# rpi_can.net
KiCad netlist of a schematic drawn in EAGLE
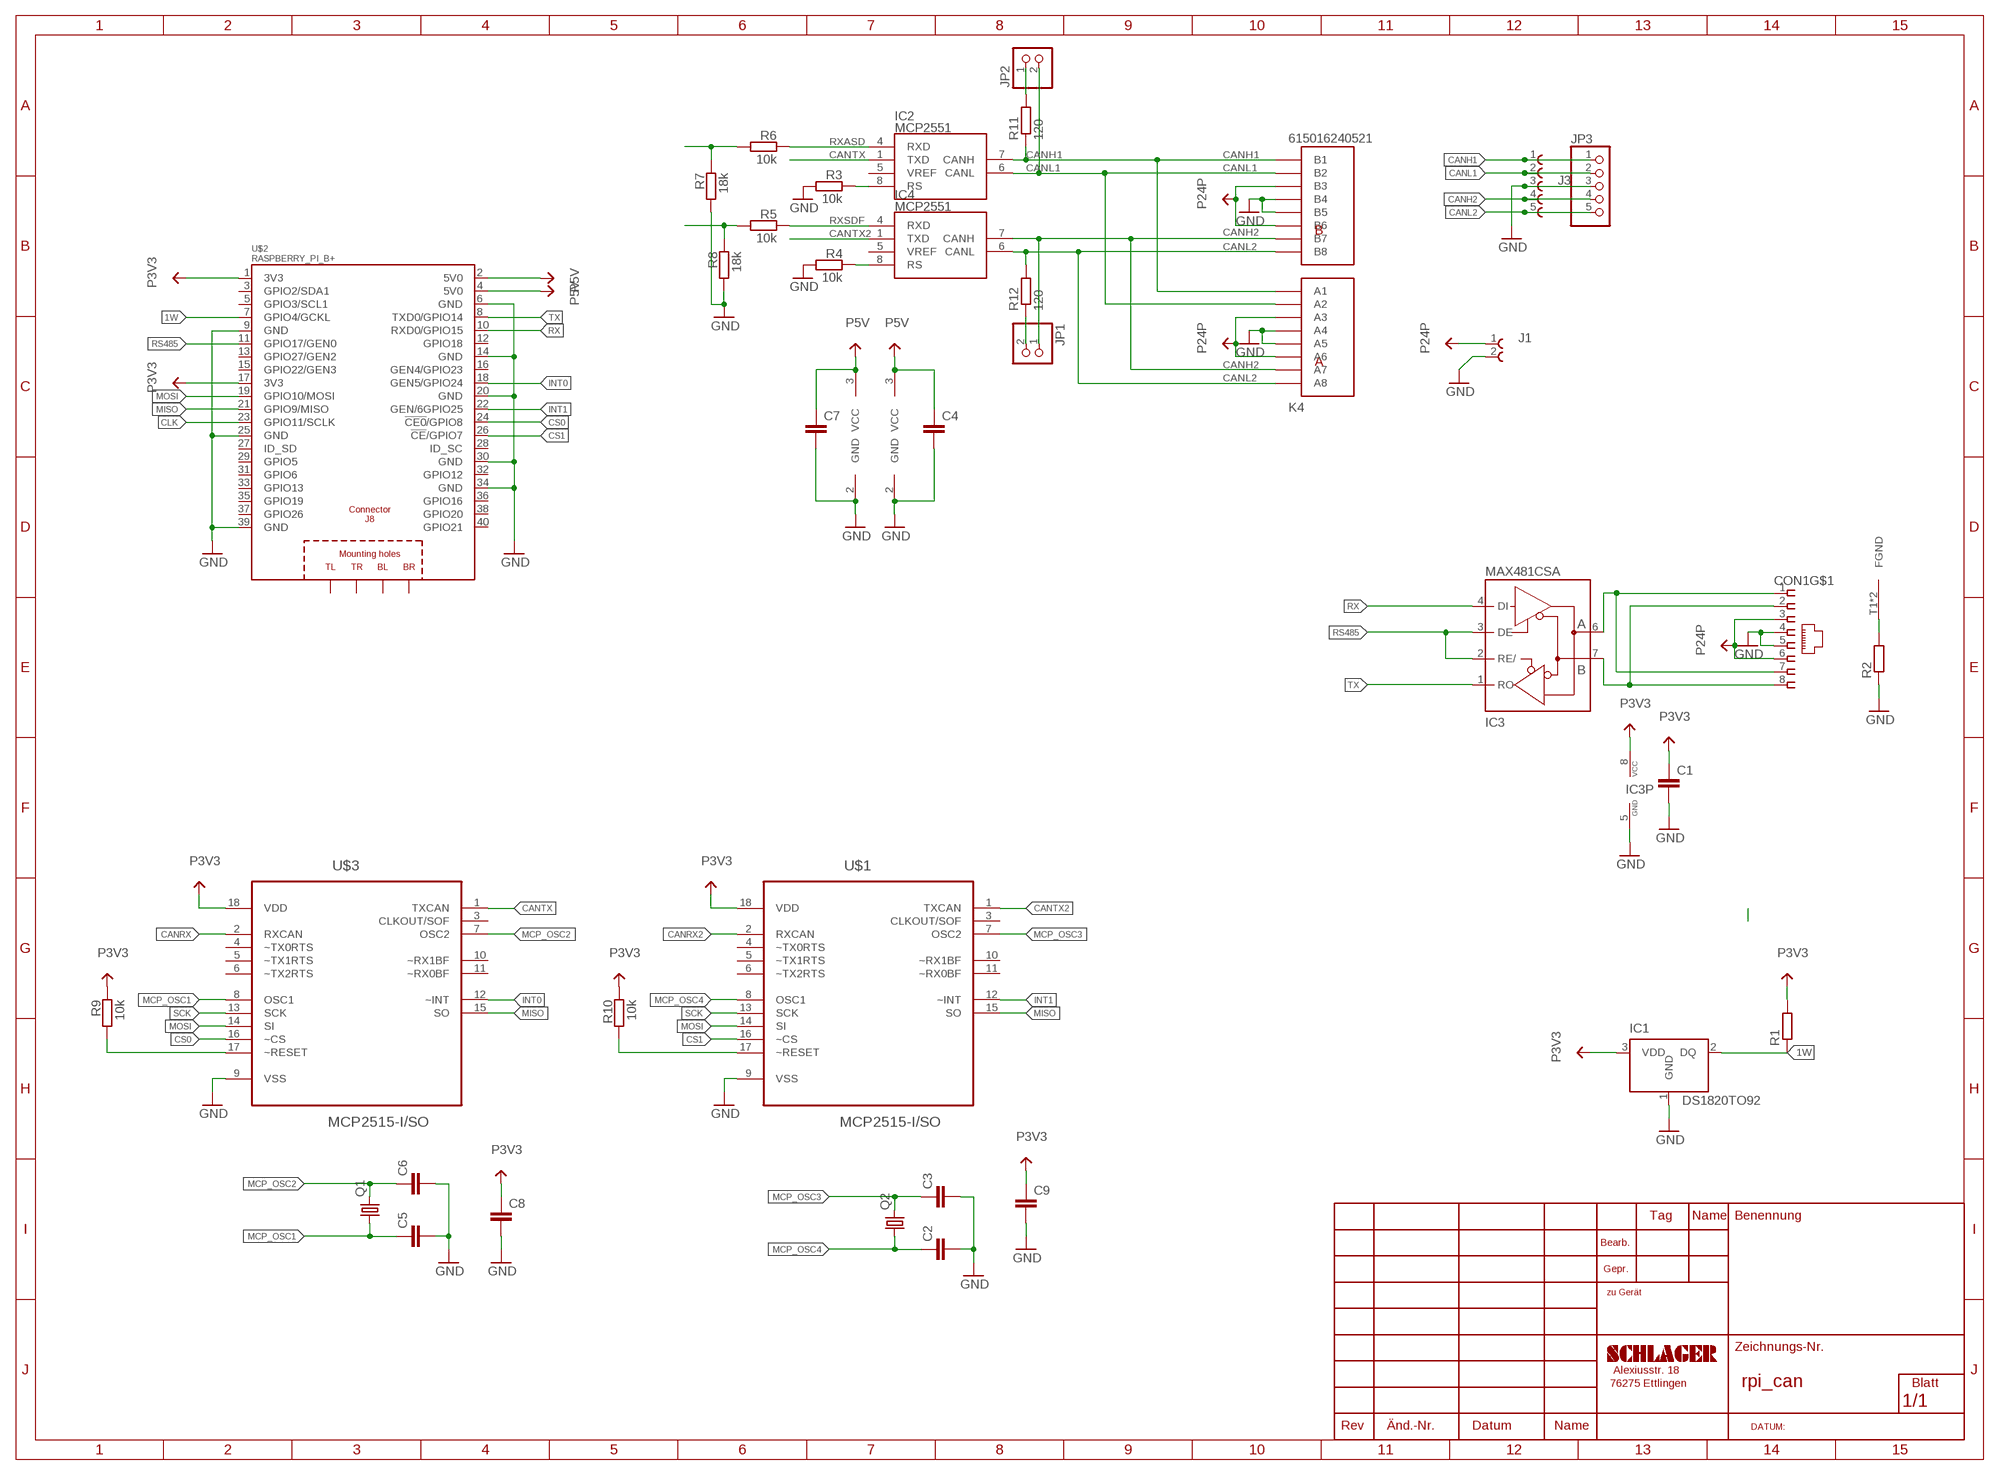
[diagram p0: schematic, sheet 1]

(export (version "E")
  (design (tool "Eeschema 10.0.6"))
  (components
    (comp (ref "C1")
      (value "C-EUC0805")
      (footprint "eagle-import:C0805")
      (libsource (lib "eagle-import") (part "C-EUC0805"))
    )
    (comp (ref "C2")
      (value "C-EUC0805")
      (footprint "eagle-import:C0805")
      (libsource (lib "eagle-import") (part "C-EUC0805"))
    )
    (comp (ref "C3")
      (value "C-EUC0805")
      (footprint "eagle-import:C0805")
      (libsource (lib "eagle-import") (part "C-EUC0805"))
    )
    (comp (ref "C4")
      (value "C-EUC0805")
      (footprint "eagle-import:C0805")
      (libsource (lib "eagle-import") (part "C-EUC0805"))
    )
    (comp (ref "C5")
      (value "C-EUC0805")
      (footprint "eagle-import:C0805")
      (libsource (lib "eagle-import") (part "C-EUC0805"))
    )
    (comp (ref "C6")
      (value "C-EUC0805")
      (footprint "eagle-import:C0805")
      (libsource (lib "eagle-import") (part "C-EUC0805"))
    )
    (comp (ref "C7")
      (value "C-EUC0805")
      (footprint "eagle-import:C0805")
      (libsource (lib "eagle-import") (part "C-EUC0805"))
    )
    (comp (ref "C8")
      (value "C-EUC0805")
      (footprint "eagle-import:C0805")
      (libsource (lib "eagle-import") (part "C-EUC0805"))
    )
    (comp (ref "C9")
      (value "C-EUC0805")
      (footprint "eagle-import:C0805")
      (libsource (lib "eagle-import") (part "C-EUC0805"))
    )
    (comp (ref "CON1")
      (value "MEBP_8-8G")
      (footprint "eagle-import:MEBP")
      (libsource (lib "eagle-import") (part "MEBP_8-8G"))
    )
    (comp (ref "IC1")
      (value "DS1820TO92")
      (footprint "eagle-import:TO-92")
      (libsource (lib "eagle-import") (part "DS1820TO92"))
    )
    (comp (ref "IC2")
      (value "MCP2551")
      (footprint "eagle-import:SO-8")
      (libsource (lib "eagle-import") (part "MCP2551"))
    )
    (comp (ref "IC3")
      (value "MAX481CSA")
      (footprint "eagle-import:SO08")
      (fields (field (name "MF") "MAXIM"))
      (libsource (lib "eagle-import") (part "MAX481CSA"))
    )
    (comp (ref "IC4")
      (value "MCP2551")
      (footprint "eagle-import:SO-8")
      (libsource (lib "eagle-import") (part "MCP2551"))
    )
    (comp (ref "J1")
      (value "691322310002")
      (footprint "eagle-import:691322310002")
      (libsource (lib "eagle-import") (part "691322310002"))
    )
    (comp (ref "J3")
      (value "691322310005")
      (footprint "eagle-import:691322310005")
      (libsource (lib "eagle-import") (part "691322310005"))
    )
    (comp (ref "JP1")
      (value "PINHD-1X2")
      (footprint "eagle-import:1X02")
      (libsource (lib "eagle-import") (part "PINHD-1X2"))
    )
    (comp (ref "JP2")
      (value "PINHD-1X2")
      (footprint "eagle-import:1X02")
      (libsource (lib "eagle-import") (part "PINHD-1X2"))
    )
    (comp (ref "JP3")
      (value "PINHD-1X5")
      (footprint "eagle-import:1X05")
      (libsource (lib "eagle-import") (part "PINHD-1X5"))
    )
    (comp (ref "K4")
      (value "615016240521")
      (footprint "eagle-import:615016240521")
      (libsource (lib "eagle-import") (part "615016240521"))
    )
    (comp (ref "Q1")
      (value "CRYSTALHC49S")
      (footprint "eagle-import:HC49_S")
      (libsource (lib "eagle-import") (part "CRYSTALHC49S"))
    )
    (comp (ref "Q2")
      (value "CRYSTALHC49S")
      (footprint "eagle-import:HC49_S")
      (libsource (lib "eagle-import") (part "CRYSTALHC49S"))
    )
    (comp (ref "R1")
      (value "R-EU_R0805")
      (footprint "eagle-import:R0805")
      (libsource (lib "eagle-import") (part "R-EU_R0805"))
    )
    (comp (ref "R2")
      (value "R-EU_R0805")
      (footprint "eagle-import:R0805")
      (libsource (lib "eagle-import") (part "R-EU_R0805"))
    )
    (comp (ref "R3")
      (value "10k")
      (footprint "eagle-import:R0805")
      (libsource (lib "eagle-import") (part "R-EU_R0805"))
    )
    (comp (ref "R4")
      (value "10k")
      (footprint "eagle-import:R0805")
      (libsource (lib "eagle-import") (part "R-EU_R0805"))
    )
    (comp (ref "R5")
      (value "10k")
      (footprint "eagle-import:R0805")
      (libsource (lib "eagle-import") (part "R-EU_R0805"))
    )
    (comp (ref "R6")
      (value "10k")
      (footprint "eagle-import:R0805")
      (libsource (lib "eagle-import") (part "R-EU_R0805"))
    )
    (comp (ref "R7")
      (value "18k")
      (footprint "eagle-import:R0805")
      (libsource (lib "eagle-import") (part "R-EU_R0805"))
    )
    (comp (ref "R8")
      (value "18k")
      (footprint "eagle-import:R0805")
      (libsource (lib "eagle-import") (part "R-EU_R0805"))
    )
    (comp (ref "R9")
      (value "10k")
      (footprint "eagle-import:R0805")
      (libsource (lib "eagle-import") (part "R-EU_R0805"))
    )
    (comp (ref "R10")
      (value "10k")
      (footprint "eagle-import:R0805")
      (libsource (lib "eagle-import") (part "R-EU_R0805"))
    )
    (comp (ref "R11")
      (value "120")
      (footprint "eagle-import:R0805")
      (libsource (lib "eagle-import") (part "R-EU_R0805"))
    )
    (comp (ref "R12")
      (value "120")
      (footprint "eagle-import:R0805")
      (libsource (lib "eagle-import") (part "R-EU_R0805"))
    )
    (comp (ref "U$1")
      (value "MCP2515-I/SO")
      (footprint "eagle-import:SOIC127P1034X264-18N")
      (libsource (lib "eagle-import") (part "MCP2515-I/SO"))
    )
    (comp (ref "U$2")
      (value "RASPBERRY_PI_B+")
      (footprint "eagle-import:RASPBERRY_PI_B+")
      (libsource (lib "eagle-import") (part "RASPBERRY_PI_B+"))
    )
    (comp (ref "U$3")
      (value "MCP2515-I/SO")
      (footprint "eagle-import:SOIC127P1034X264-18N")
      (libsource (lib "eagle-import") (part "MCP2515-I/SO"))
    )
  )
  (nets
    (net (code "1") (name "/RXASD") (class "Default")
      (node (ref "IC2") (pin "4") (pinfunction "RXD_4") (pintype "bidirectional"))
      (node (ref "R6") (pin "1") (pinfunction "1_1") (pintype "passive"))
    )
    (net (code "2") (name "/RXSDF") (class "Default")
      (node (ref "IC4") (pin "4") (pinfunction "RXD_4") (pintype "bidirectional"))
      (node (ref "R5") (pin "1") (pinfunction "1_1") (pintype "passive"))
    )
    (net (code "3") (name "1W") (class "Default")
      (node (ref "IC1") (pin "2") (pinfunction "DQ_2") (pintype "output"))
      (node (ref "R1") (pin "1") (pinfunction "1_1") (pintype "passive"))
      (node (ref "U$2") (pin "7") (pinfunction "GPIO4/GCKL_7") (pintype "bidirectional"))
    )
    (net (code "4") (name "CANH1") (class "Default")
      (node (ref "IC2") (pin "7") (pinfunction "CANH_7") (pintype "bidirectional"))
      (node (ref "J3") (pin "1") (pinfunction "1_1") (pintype "passive"))
      (node (ref "JP3") (pin "1") (pinfunction "1_1") (pintype "passive"))
      (node (ref "K4") (pin "A1") (pinfunction "A1_A1") (pintype "passive"))
      (node (ref "K4") (pin "B1") (pinfunction "B1_B1") (pintype "passive"))
      (node (ref "R11") (pin "1") (pinfunction "1_1") (pintype "passive"))
    )
    (net (code "5") (name "CANH2") (class "Default")
      (node (ref "IC4") (pin "7") (pinfunction "CANH_7") (pintype "bidirectional"))
      (node (ref "J3") (pin "4") (pinfunction "4_4") (pintype "passive"))
      (node (ref "JP1") (pin "1") (pinfunction "1_1") (pintype "passive"))
      (node (ref "JP3") (pin "4") (pinfunction "4_4") (pintype "passive"))
      (node (ref "K4") (pin "A7") (pinfunction "A7_A7") (pintype "passive"))
      (node (ref "K4") (pin "B7") (pinfunction "B7_B7") (pintype "passive"))
    )
    (net (code "6") (name "CANL1") (class "Default")
      (node (ref "IC2") (pin "6") (pinfunction "CANL_6") (pintype "bidirectional"))
      (node (ref "J3") (pin "2") (pinfunction "2_2") (pintype "passive"))
      (node (ref "JP2") (pin "2") (pinfunction "2_2") (pintype "passive"))
      (node (ref "JP3") (pin "2") (pinfunction "2_2") (pintype "passive"))
      (node (ref "K4") (pin "A2") (pinfunction "A2_A2") (pintype "passive"))
      (node (ref "K4") (pin "B2") (pinfunction "B2_B2") (pintype "passive"))
    )
    (net (code "7") (name "CANL2") (class "Default")
      (node (ref "IC4") (pin "6") (pinfunction "CANL_6") (pintype "bidirectional"))
      (node (ref "J3") (pin "5") (pinfunction "5_5") (pintype "passive"))
      (node (ref "JP3") (pin "5") (pinfunction "5_5") (pintype "passive"))
      (node (ref "K4") (pin "A8") (pinfunction "A8_A8") (pintype "passive"))
      (node (ref "K4") (pin "B8") (pinfunction "B8_B8") (pintype "passive"))
      (node (ref "R12") (pin "2") (pinfunction "2_2") (pintype "passive"))
    )
    (net (code "8") (name "CANRX") (class "Default")
      (node (ref "R6") (pin "2") (pinfunction "2_2") (pintype "passive"))
      (node (ref "R7") (pin "1") (pinfunction "1_1") (pintype "passive"))
      (node (ref "U$3") (pin "2") (pinfunction "RXCAN_2") (pintype "input"))
    )
    (net (code "9") (name "CANRX2") (class "Default")
      (node (ref "R5") (pin "2") (pinfunction "2_2") (pintype "passive"))
      (node (ref "R8") (pin "1") (pinfunction "1_1") (pintype "passive"))
      (node (ref "U$1") (pin "2") (pinfunction "RXCAN_2") (pintype "input"))
    )
    (net (code "10") (name "CANTX") (class "Default")
      (node (ref "IC2") (pin "1") (pinfunction "TXD_1") (pintype "bidirectional"))
      (node (ref "U$3") (pin "1") (pinfunction "TXCAN_1") (pintype "output"))
    )
    (net (code "11") (name "CANTX2") (class "Default")
      (node (ref "IC4") (pin "1") (pinfunction "TXD_1") (pintype "bidirectional"))
      (node (ref "U$1") (pin "1") (pinfunction "TXCAN_1") (pintype "output"))
    )
    (net (code "12") (name "CLK") (class "Default")
      (node (ref "U$2") (pin "23") (pinfunction "GPIO11/SCLK_23") (pintype "bidirectional"))
    )
    (net (code "13") (name "CS0") (class "Default")
      (node (ref "U$2") (pin "24") (pinfunction "~{CE0}/GPIO8_24") (pintype "bidirectional"))
      (node (ref "U$3") (pin "16") (pinfunction "~{CS}_16") (pintype "input"))
    )
    (net (code "14") (name "CS1") (class "Default")
      (node (ref "U$1") (pin "16") (pinfunction "~{CS}_16") (pintype "input"))
      (node (ref "U$2") (pin "26") (pinfunction "~{CE}/GPIO7_26") (pintype "bidirectional"))
    )
    (net (code "15") (name "GND") (class "Default")
      (node (ref "C1") (pin "2") (pinfunction "2_2") (pintype "passive"))
      (node (ref "C2") (pin "2") (pinfunction "2_2") (pintype "passive"))
      (node (ref "C3") (pin "2") (pinfunction "2_2") (pintype "passive"))
      (node (ref "C4") (pin "2") (pinfunction "2_2") (pintype "passive"))
      (node (ref "C5") (pin "2") (pinfunction "2_2") (pintype "passive"))
      (node (ref "C6") (pin "2") (pinfunction "2_2") (pintype "passive"))
      (node (ref "C7") (pin "2") (pinfunction "2_2") (pintype "passive"))
      (node (ref "C8") (pin "2") (pinfunction "2_2") (pintype "passive"))
      (node (ref "C9") (pin "2") (pinfunction "2_2") (pintype "passive"))
      (node (ref "CON1") (pin "4") (pinfunction "4_4") (pintype "passive"))
      (node (ref "CON1") (pin "5") (pinfunction "5_5") (pintype "passive"))
      (node (ref "IC1") (pin "1") (pinfunction "GND_1") (pintype "power_in"))
      (node (ref "IC2") (pin "2") (pinfunction "GND_2") (pintype "power_in"))
      (node (ref "IC3") (pin "5") (pinfunction "GND_5") (pintype "power_in"))
      (node (ref "IC4") (pin "2") (pinfunction "GND_2") (pintype "power_in"))
      (node (ref "J1") (pin "2") (pinfunction "2_2") (pintype "passive"))
      (node (ref "J3") (pin "3") (pinfunction "3_3") (pintype "passive"))
      (node (ref "JP3") (pin "3") (pinfunction "3_3") (pintype "passive"))
      (node (ref "K4") (pin "A4") (pinfunction "A4_A4") (pintype "passive"))
      (node (ref "K4") (pin "A5") (pinfunction "A5_A5") (pintype "passive"))
      (node (ref "K4") (pin "B4") (pinfunction "B4_B4") (pintype "passive"))
      (node (ref "K4") (pin "B5") (pinfunction "B5_B5") (pintype "passive"))
      (node (ref "R2") (pin "1") (pinfunction "1_1") (pintype "passive"))
      (node (ref "R3") (pin "2") (pinfunction "2_2") (pintype "passive"))
      (node (ref "R4") (pin "2") (pinfunction "2_2") (pintype "passive"))
      (node (ref "R7") (pin "2") (pinfunction "2_2") (pintype "passive"))
      (node (ref "R8") (pin "2") (pinfunction "2_2") (pintype "passive"))
      (node (ref "U$1") (pin "9") (pinfunction "VSS_9") (pintype "power_in"))
      (node (ref "U$2") (pin "14") (pinfunction "GND_14") (pintype "power_in"))
      (node (ref "U$2") (pin "20") (pinfunction "GND_20") (pintype "power_in"))
      (node (ref "U$2") (pin "25") (pinfunction "GND_25") (pintype "power_in"))
      (node (ref "U$2") (pin "30") (pinfunction "GND_30") (pintype "power_in"))
      (node (ref "U$2") (pin "34") (pinfunction "GND_34") (pintype "power_in"))
      (node (ref "U$2") (pin "39") (pinfunction "GND_39") (pintype "power_in"))
      (node (ref "U$2") (pin "6") (pinfunction "GND_6") (pintype "power_in"))
      (node (ref "U$2") (pin "9") (pinfunction "GND_9") (pintype "power_in"))
      (node (ref "U$3") (pin "9") (pinfunction "VSS_9") (pintype "power_in"))
    )
    (net (code "16") (name "INT0") (class "Default")
      (node (ref "U$2") (pin "18") (pinfunction "GEN5/GPIO24_18") (pintype "bidirectional"))
      (node (ref "U$3") (pin "12") (pinfunction "~{INT}_12") (pintype "output"))
    )
    (net (code "17") (name "INT1") (class "Default")
      (node (ref "U$1") (pin "12") (pinfunction "~{INT}_12") (pintype "output"))
      (node (ref "U$2") (pin "22") (pinfunction "GEN/6GPIO25_22") (pintype "bidirectional"))
    )
    (net (code "18") (name "MCP_OSC1") (class "Default")
      (node (ref "C5") (pin "1") (pinfunction "1_1") (pintype "passive"))
      (node (ref "Q1") (pin "1") (pinfunction "1_1") (pintype "passive"))
      (node (ref "U$3") (pin "8") (pinfunction "OSC1_8") (pintype "input"))
    )
    (net (code "19") (name "MCP_OSC2") (class "Default")
      (node (ref "C6") (pin "1") (pinfunction "1_1") (pintype "passive"))
      (node (ref "Q1") (pin "2") (pinfunction "2_2") (pintype "passive"))
      (node (ref "U$3") (pin "7") (pinfunction "OSC2_7") (pintype "output"))
    )
    (net (code "20") (name "MCP_OSC3") (class "Default")
      (node (ref "C3") (pin "1") (pinfunction "1_1") (pintype "passive"))
      (node (ref "Q2") (pin "2") (pinfunction "2_2") (pintype "passive"))
      (node (ref "U$1") (pin "7") (pinfunction "OSC2_7") (pintype "output"))
    )
    (net (code "21") (name "MCP_OSC4") (class "Default")
      (node (ref "C2") (pin "1") (pinfunction "1_1") (pintype "passive"))
      (node (ref "Q2") (pin "1") (pinfunction "1_1") (pintype "passive"))
      (node (ref "U$1") (pin "8") (pinfunction "OSC1_8") (pintype "input"))
    )
    (net (code "22") (name "MISO") (class "Default")
      (node (ref "U$1") (pin "15") (pinfunction "SO_15") (pintype "output"))
      (node (ref "U$2") (pin "21") (pinfunction "GPIO9/MISO_21") (pintype "bidirectional"))
      (node (ref "U$3") (pin "15") (pinfunction "SO_15") (pintype "output"))
    )
    (net (code "23") (name "MOSI") (class "Default")
      (node (ref "U$1") (pin "14") (pinfunction "SI_14") (pintype "input"))
      (node (ref "U$2") (pin "19") (pinfunction "GPIO10/MOSI_19") (pintype "bidirectional"))
      (node (ref "U$3") (pin "14") (pinfunction "SI_14") (pintype "input"))
    )
    (net (code "24") (name "Net-(CON1B-FGND-PadT1)") (class "Default")
      (node (ref "CON1") (pin "T1") (pinfunction "FGND_T1") (pintype "power_in"))
      (node (ref "CON1") (pin "T2") (pinfunction "FGND_T2") (pintype "power_in"))
      (node (ref "R2") (pin "2") (pinfunction "2_2") (pintype "passive"))
    )
    (net (code "25") (name "Net-(IC2A-RS)") (class "Default")
      (node (ref "IC2") (pin "8") (pinfunction "RS_8") (pintype "bidirectional"))
      (node (ref "R3") (pin "1") (pinfunction "1_1") (pintype "passive"))
    )
    (net (code "26") (name "Net-(IC3A-A)") (class "Default")
      (node (ref "CON1") (pin "1") (pinfunction "1_1") (pintype "passive"))
      (node (ref "CON1") (pin "7") (pinfunction "7_7") (pintype "passive"))
      (node (ref "IC3") (pin "6") (pinfunction "A_6") (pintype "passive"))
    )
    (net (code "27") (name "Net-(IC3A-B)") (class "Default")
      (node (ref "CON1") (pin "2") (pinfunction "2_2") (pintype "passive"))
      (node (ref "CON1") (pin "8") (pinfunction "8_8") (pintype "passive"))
      (node (ref "IC3") (pin "7") (pinfunction "B_7") (pintype "passive"))
    )
    (net (code "28") (name "Net-(IC4A-RS)") (class "Default")
      (node (ref "IC4") (pin "8") (pinfunction "RS_8") (pintype "bidirectional"))
      (node (ref "R4") (pin "1") (pinfunction "1_1") (pintype "passive"))
    )
    (net (code "29") (name "Net-(JP1-Pad2)") (class "Default")
      (node (ref "JP1") (pin "2") (pinfunction "2_2") (pintype "passive"))
      (node (ref "R12") (pin "1") (pinfunction "1_1") (pintype "passive"))
    )
    (net (code "30") (name "Net-(JP2-Pad1)") (class "Default")
      (node (ref "JP2") (pin "1") (pinfunction "1_1") (pintype "passive"))
      (node (ref "R11") (pin "2") (pinfunction "2_2") (pintype "passive"))
    )
    (net (code "31") (name "Net-(U$1-~{RESET})") (class "Default")
      (node (ref "R10") (pin "2") (pinfunction "2_2") (pintype "passive"))
      (node (ref "U$1") (pin "17") (pinfunction "~{RESET}_17") (pintype "input"))
    )
    (net (code "32") (name "Net-(U$3-~{RESET})") (class "Default")
      (node (ref "R9") (pin "2") (pinfunction "2_2") (pintype "passive"))
      (node (ref "U$3") (pin "17") (pinfunction "~{RESET}_17") (pintype "input"))
    )
    (net (code "33") (name "P3V3") (class "Default")
      (node (ref "C1") (pin "1") (pinfunction "1_1") (pintype "passive"))
      (node (ref "C8") (pin "1") (pinfunction "1_1") (pintype "passive"))
      (node (ref "C9") (pin "1") (pinfunction "1_1") (pintype "passive"))
      (node (ref "IC1") (pin "3") (pinfunction "VDD_3") (pintype "input"))
      (node (ref "IC3") (pin "8") (pinfunction "VCC_8") (pintype "power_in"))
      (node (ref "R1") (pin "2") (pinfunction "2_2") (pintype "passive"))
      (node (ref "R10") (pin "1") (pinfunction "1_1") (pintype "passive"))
      (node (ref "R9") (pin "1") (pinfunction "1_1") (pintype "passive"))
      (node (ref "U$1") (pin "18") (pinfunction "VDD_18") (pintype "power_in"))
      (node (ref "U$2") (pin "1") (pinfunction "3V3_1") (pintype "power_in"))
      (node (ref "U$2") (pin "17") (pinfunction "3V3_17") (pintype "power_in"))
      (node (ref "U$3") (pin "18") (pinfunction "VDD_18") (pintype "power_in"))
    )
    (net (code "34") (name "P5V") (class "Default")
      (node (ref "C4") (pin "1") (pinfunction "1_1") (pintype "passive"))
      (node (ref "C7") (pin "1") (pinfunction "1_1") (pintype "passive"))
      (node (ref "IC2") (pin "3") (pinfunction "VCC_3") (pintype "power_in"))
      (node (ref "IC4") (pin "3") (pinfunction "VCC_3") (pintype "power_in"))
      (node (ref "U$2") (pin "2") (pinfunction "5V0_2") (pintype "power_in"))
      (node (ref "U$2") (pin "4") (pinfunction "5V0_4") (pintype "power_in"))
    )
    (net (code "35") (name "P24P") (class "Default")
      (node (ref "CON1") (pin "3") (pinfunction "3_3") (pintype "passive"))
      (node (ref "CON1") (pin "6") (pinfunction "6_6") (pintype "passive"))
      (node (ref "J1") (pin "1") (pinfunction "1_1") (pintype "passive"))
      (node (ref "K4") (pin "A3") (pinfunction "A3_A3") (pintype "passive"))
      (node (ref "K4") (pin "A6") (pinfunction "A6_A6") (pintype "passive"))
      (node (ref "K4") (pin "B3") (pinfunction "B3_B3") (pintype "passive"))
      (node (ref "K4") (pin "B6") (pinfunction "B6_B6") (pintype "passive"))
    )
    (net (code "36") (name "RS485") (class "Default")
      (node (ref "IC3") (pin "2") (pinfunction "RE/_2") (pintype "input"))
      (node (ref "IC3") (pin "3") (pinfunction "DE_3") (pintype "input"))
      (node (ref "U$2") (pin "11") (pinfunction "GPIO17/GEN0_11") (pintype "bidirectional"))
    )
    (net (code "37") (name "RX") (class "Default")
      (node (ref "IC3") (pin "4") (pinfunction "DI_4") (pintype "input"))
      (node (ref "U$2") (pin "10") (pinfunction "RXD0/GPIO15_10") (pintype "bidirectional"))
    )
    (net (code "38") (name "SCK") (class "Default")
      (node (ref "U$1") (pin "13") (pinfunction "SCK_13") (pintype "input"))
      (node (ref "U$3") (pin "13") (pinfunction "SCK_13") (pintype "input"))
    )
    (net (code "39") (name "TX") (class "Default")
      (node (ref "IC3") (pin "1") (pinfunction "RO_1") (pintype "output"))
      (node (ref "U$2") (pin "8") (pinfunction "TXD0/GPIO14_8") (pintype "bidirectional"))
    )
    (net (code "40") (name "unconnected-(IC2A-VREF-Pad5)") (class "Default")
      (node (ref "IC2") (pin "5") (pinfunction "VREF_5") (pintype "bidirectional"))
    )
    (net (code "41") (name "unconnected-(IC4A-VREF-Pad5)") (class "Default")
      (node (ref "IC4") (pin "5") (pinfunction "VREF_5") (pintype "bidirectional"))
    )
    (net (code "42") (name "unconnected-(U$1-CLKOUT{slash}SOF-Pad3)") (class "Default")
      (node (ref "U$1") (pin "3") (pinfunction "CLKOUT/SOF_3") (pintype "output"))
    )
    (net (code "43") (name "unconnected-(U$1-~{RX0BF}-Pad11)") (class "Default")
      (node (ref "U$1") (pin "11") (pinfunction "~{RX0BF}_11") (pintype "output"))
    )
    (net (code "44") (name "unconnected-(U$1-~{RX1BF}-Pad10)") (class "Default")
      (node (ref "U$1") (pin "10") (pinfunction "~{RX1BF}_10") (pintype "output"))
    )
    (net (code "45") (name "unconnected-(U$1-~{TX0RTS}-Pad4)") (class "Default")
      (node (ref "U$1") (pin "4") (pinfunction "~{TX0RTS}_4") (pintype "input"))
    )
    (net (code "46") (name "unconnected-(U$1-~{TX1RTS}-Pad5)") (class "Default")
      (node (ref "U$1") (pin "5") (pinfunction "~{TX1RTS}_5") (pintype "input"))
    )
    (net (code "47") (name "unconnected-(U$1-~{TX2RTS}-Pad6)") (class "Default")
      (node (ref "U$1") (pin "6") (pinfunction "~{TX2RTS}_6") (pintype "input"))
    )
    (net (code "48") (name "unconnected-(U$2-BL-PadPE_BL)") (class "Default")
      (node (ref "U$2") (pin "PE_BL") (pinfunction "BL_PE_BL") (pintype "bidirectional"))
    )
    (net (code "49") (name "unconnected-(U$2-BR-PadPE_BR)") (class "Default")
      (node (ref "U$2") (pin "PE_BR") (pinfunction "BR_PE_BR") (pintype "bidirectional"))
    )
    (net (code "50") (name "unconnected-(U$2-GEN4{slash}GPIO23-Pad16)") (class "Default")
      (node (ref "U$2") (pin "16") (pinfunction "GEN4/GPIO23_16") (pintype "bidirectional"))
    )
    (net (code "51") (name "unconnected-(U$2-GPIO2{slash}SDA1-Pad3)") (class "Default")
      (node (ref "U$2") (pin "3") (pinfunction "GPIO2/SDA1_3") (pintype "bidirectional"))
    )
    (net (code "52") (name "unconnected-(U$2-GPIO3{slash}SCL1-Pad5)") (class "Default")
      (node (ref "U$2") (pin "5") (pinfunction "GPIO3/SCL1_5") (pintype "bidirectional"))
    )
    (net (code "53") (name "unconnected-(U$2-GPIO5-Pad29)") (class "Default")
      (node (ref "U$2") (pin "29") (pinfunction "GPIO5_29") (pintype "bidirectional"))
    )
    (net (code "54") (name "unconnected-(U$2-GPIO6-Pad31)") (class "Default")
      (node (ref "U$2") (pin "31") (pinfunction "GPIO6_31") (pintype "bidirectional"))
    )
    (net (code "55") (name "unconnected-(U$2-GPIO12-Pad32)") (class "Default")
      (node (ref "U$2") (pin "32") (pinfunction "GPIO12_32") (pintype "bidirectional"))
    )
    (net (code "56") (name "unconnected-(U$2-GPIO13-Pad33)") (class "Default")
      (node (ref "U$2") (pin "33") (pinfunction "GPIO13_33") (pintype "bidirectional"))
    )
    (net (code "57") (name "unconnected-(U$2-GPIO16-Pad36)") (class "Default")
      (node (ref "U$2") (pin "36") (pinfunction "GPIO16_36") (pintype "bidirectional"))
    )
    (net (code "58") (name "unconnected-(U$2-GPIO18-Pad12)") (class "Default")
      (node (ref "U$2") (pin "12") (pinfunction "GPIO18_12") (pintype "bidirectional"))
    )
    (net (code "59") (name "unconnected-(U$2-GPIO19-Pad35)") (class "Default")
      (node (ref "U$2") (pin "35") (pinfunction "GPIO19_35") (pintype "bidirectional"))
    )
    (net (code "60") (name "unconnected-(U$2-GPIO20-Pad38)") (class "Default")
      (node (ref "U$2") (pin "38") (pinfunction "GPIO20_38") (pintype "bidirectional"))
    )
    (net (code "61") (name "unconnected-(U$2-GPIO21-Pad40)") (class "Default")
      (node (ref "U$2") (pin "40") (pinfunction "GPIO21_40") (pintype "bidirectional"))
    )
    (net (code "62") (name "unconnected-(U$2-GPIO22{slash}GEN3-Pad15)") (class "Default")
      (node (ref "U$2") (pin "15") (pinfunction "GPIO22/GEN3_15") (pintype "bidirectional"))
    )
    (net (code "63") (name "unconnected-(U$2-GPIO26-Pad37)") (class "Default")
      (node (ref "U$2") (pin "37") (pinfunction "GPIO26_37") (pintype "bidirectional"))
    )
    (net (code "64") (name "unconnected-(U$2-GPIO27{slash}GEN2-Pad13)") (class "Default")
      (node (ref "U$2") (pin "13") (pinfunction "GPIO27/GEN2_13") (pintype "bidirectional"))
    )
    (net (code "65") (name "unconnected-(U$2-ID_SC-Pad28)") (class "Default")
      (node (ref "U$2") (pin "28") (pinfunction "ID_SC_28") (pintype "bidirectional"))
    )
    (net (code "66") (name "unconnected-(U$2-ID_SD-Pad27)") (class "Default")
      (node (ref "U$2") (pin "27") (pinfunction "ID_SD_27") (pintype "bidirectional"))
    )
    (net (code "67") (name "unconnected-(U$2-TL-PadPE_TL)") (class "Default")
      (node (ref "U$2") (pin "PE_TL") (pinfunction "TL_PE_TL") (pintype "bidirectional"))
    )
    (net (code "68") (name "unconnected-(U$2-TR-PadPE_TR)") (class "Default")
      (node (ref "U$2") (pin "PE_TR") (pinfunction "TR_PE_TR") (pintype "bidirectional"))
    )
    (net (code "69") (name "unconnected-(U$3-CLKOUT{slash}SOF-Pad3)") (class "Default")
      (node (ref "U$3") (pin "3") (pinfunction "CLKOUT/SOF_3") (pintype "output"))
    )
    (net (code "70") (name "unconnected-(U$3-~{RX0BF}-Pad11)") (class "Default")
      (node (ref "U$3") (pin "11") (pinfunction "~{RX0BF}_11") (pintype "output"))
    )
    (net (code "71") (name "unconnected-(U$3-~{RX1BF}-Pad10)") (class "Default")
      (node (ref "U$3") (pin "10") (pinfunction "~{RX1BF}_10") (pintype "output"))
    )
    (net (code "72") (name "unconnected-(U$3-~{TX0RTS}-Pad4)") (class "Default")
      (node (ref "U$3") (pin "4") (pinfunction "~{TX0RTS}_4") (pintype "input"))
    )
    (net (code "73") (name "unconnected-(U$3-~{TX1RTS}-Pad5)") (class "Default")
      (node (ref "U$3") (pin "5") (pinfunction "~{TX1RTS}_5") (pintype "input"))
    )
    (net (code "74") (name "unconnected-(U$3-~{TX2RTS}-Pad6)") (class "Default")
      (node (ref "U$3") (pin "6") (pinfunction "~{TX2RTS}_6") (pintype "input"))
    )
  )
)
